# Keyglove_Kit_v0_1.net
KiCad netlist of a schematic drawn in EAGLE
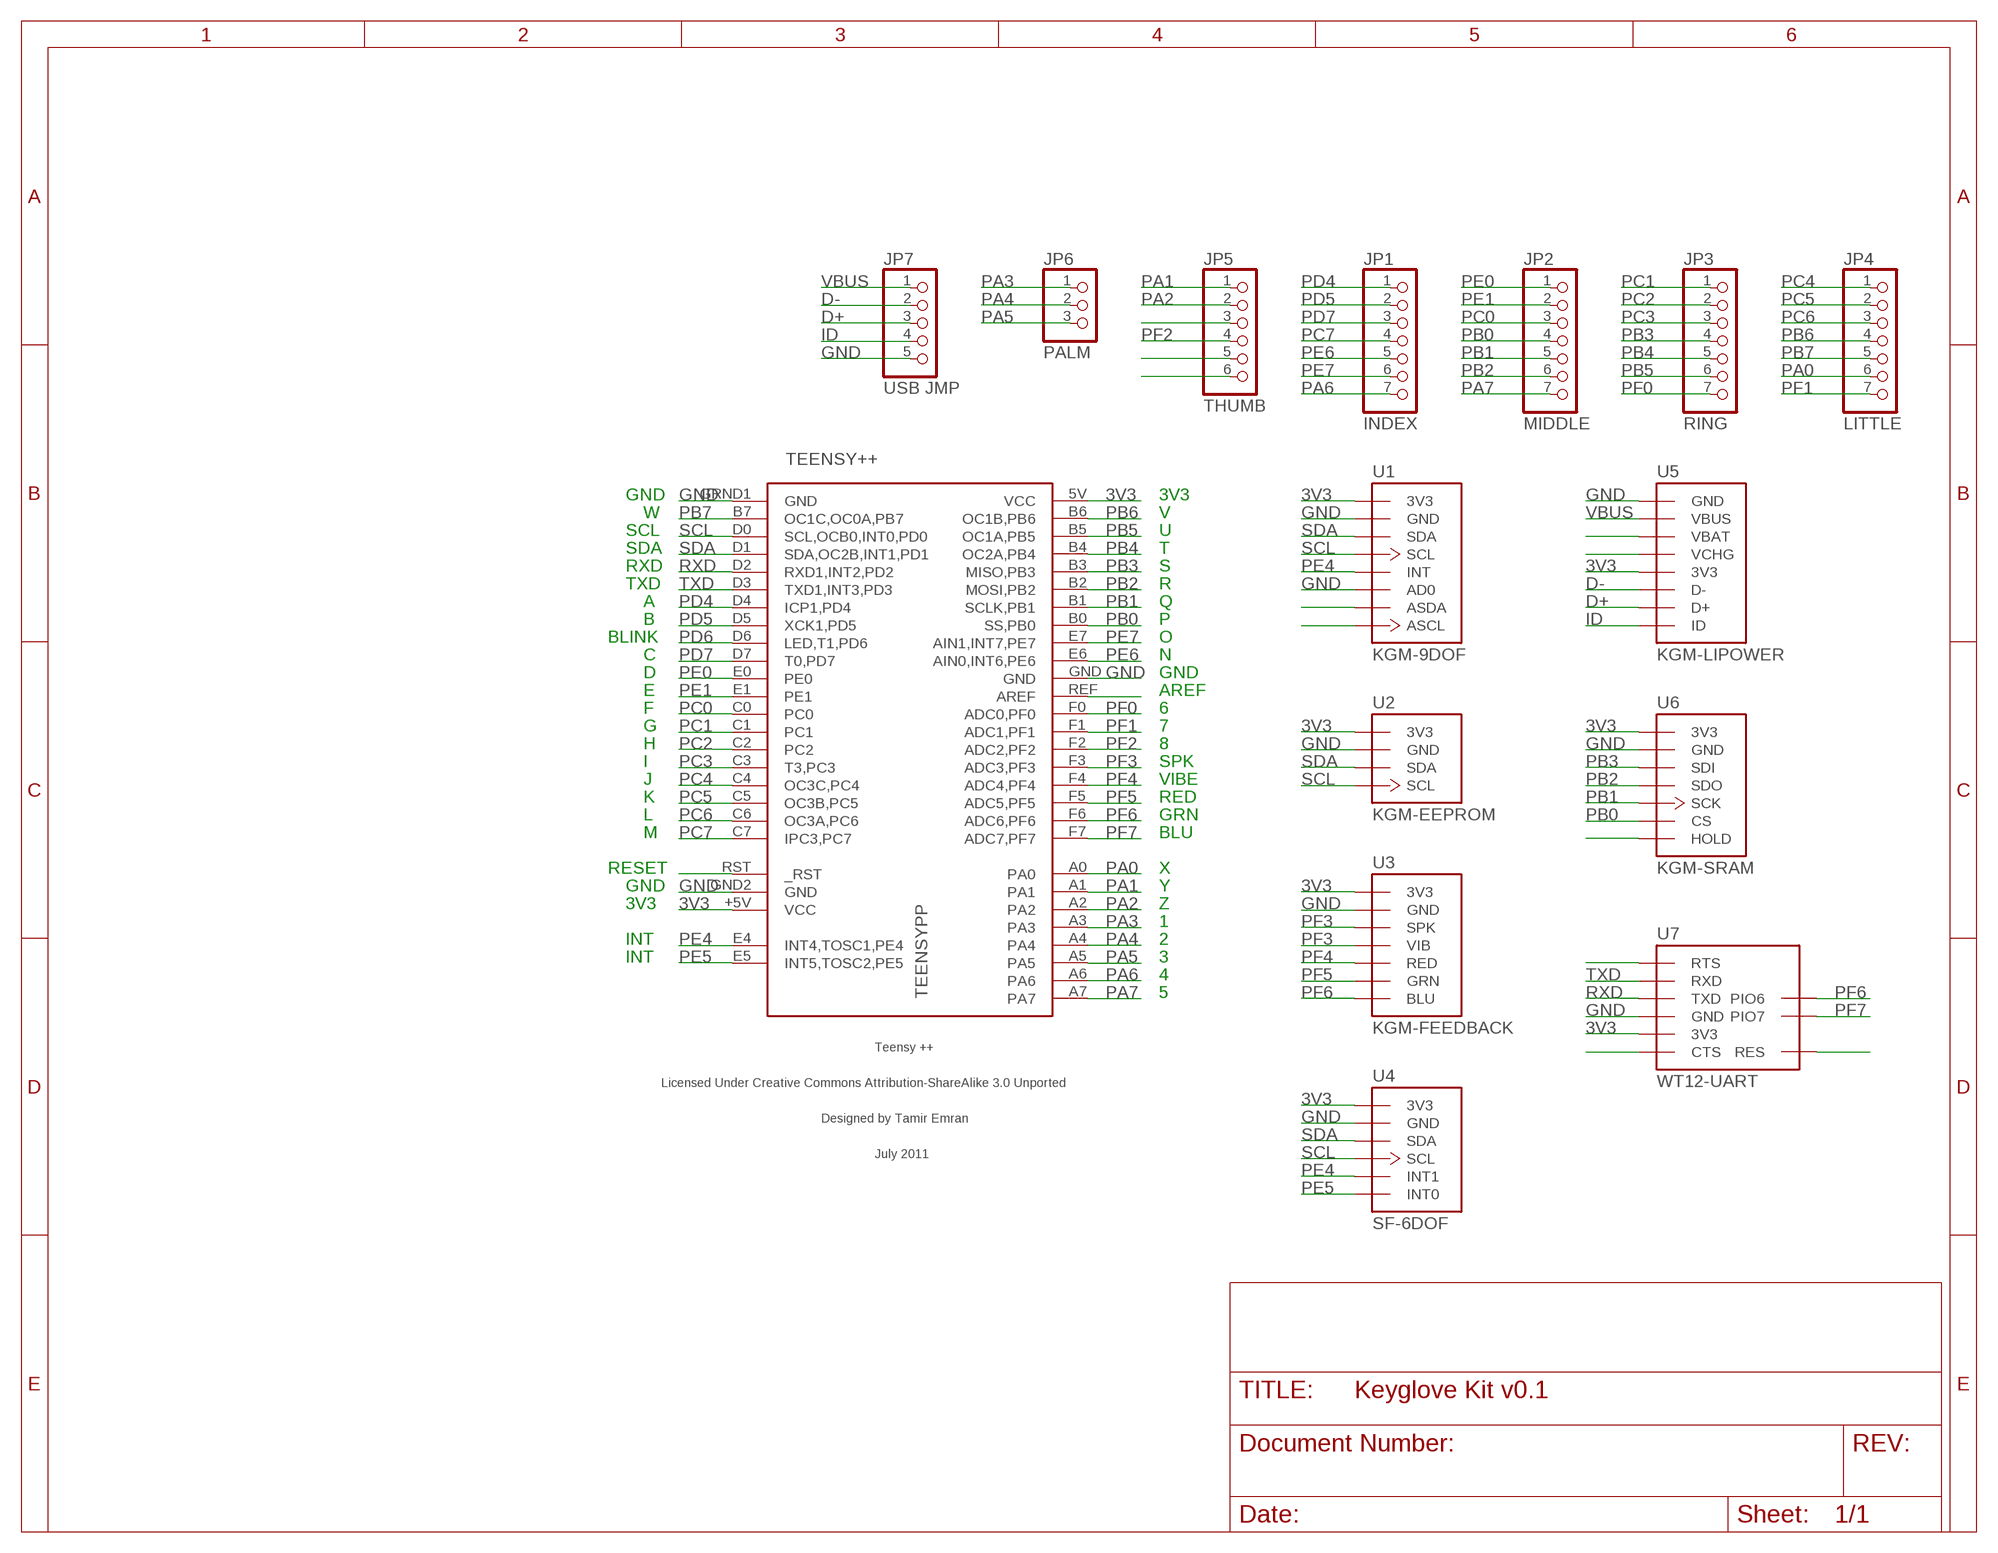
[diagram p0: schematic, sheet 1]

(export (version "E")
  (design (tool "Eeschema 10.0.6"))
  (components
    (comp (ref "JP1")
      (value "INDEX")
      (footprint "eagle-import:1X07")
      (libsource (lib "eagle-import") (part "PINHD-1X7"))
    )
    (comp (ref "JP2")
      (value "MIDDLE")
      (footprint "eagle-import:1X07")
      (libsource (lib "eagle-import") (part "PINHD-1X7"))
    )
    (comp (ref "JP3")
      (value "RING")
      (footprint "eagle-import:1X07")
      (libsource (lib "eagle-import") (part "PINHD-1X7"))
    )
    (comp (ref "JP4")
      (value "LITTLE")
      (footprint "eagle-import:1X07")
      (libsource (lib "eagle-import") (part "PINHD-1X7"))
    )
    (comp (ref "JP5")
      (value "THUMB")
      (footprint "eagle-import:1X06")
      (libsource (lib "eagle-import") (part "PINHD-1X6"))
    )
    (comp (ref "JP6")
      (value "PALM")
      (footprint "eagle-import:1X03")
      (libsource (lib "eagle-import") (part "PINHD-1X3"))
    )
    (comp (ref "JP7")
      (value "USB JMP")
      (footprint "eagle-import:1X05")
      (libsource (lib "eagle-import") (part "PINHD-1X5"))
    )
    (comp (ref "TEENSY++")
      (value "TEENSYPP")
      (footprint "eagle-import:TEENSYPP")
      (libsource (lib "eagle-import") (part "TEENSYPP"))
    )
    (comp (ref "U1")
      (value "KGM-9DOF")
      (footprint "eagle-import:KGM-9DOF")
      (libsource (lib "eagle-import") (part "KGM-9DOF"))
    )
    (comp (ref "U2")
      (value "KGM-EEPROM")
      (footprint "eagle-import:KGM-EEPROM")
      (libsource (lib "eagle-import") (part "KGM-EEPROM"))
    )
    (comp (ref "U3")
      (value "KGM-FEEDBACK")
      (footprint "eagle-import:KGM-FEEDBACK")
      (libsource (lib "eagle-import") (part "KGM-FEEDBACK"))
    )
    (comp (ref "U4")
      (value "SF-6DOF")
      (footprint "eagle-import:SF-6DOF")
      (libsource (lib "eagle-import") (part "SF-6DOF"))
    )
    (comp (ref "U5")
      (value "KGM-LIPOWER")
      (footprint "eagle-import:KGM-LIPOWER")
      (libsource (lib "eagle-import") (part "KGM-LIPOWER"))
    )
    (comp (ref "U6")
      (value "KGM-SRAM")
      (footprint "eagle-import:KGM-SRAM")
      (libsource (lib "eagle-import") (part "KGM-SRAM"))
    )
    (comp (ref "U7")
      (value "WT12-UART")
      (footprint "eagle-import:WT12-UART")
      (libsource (lib "eagle-import") (part "WT12-UART"))
    )
  )
  (nets
    (net (code "1") (name "/3V3") (class "Default")
      (node (ref "TEENSY++") (pin "+5V") (pinfunction "VCC_+5V") (pintype "power_in"))
      (node (ref "TEENSY++") (pin "5V") (pinfunction "VCC_5V") (pintype "power_in"))
      (node (ref "U1") (pin "3V3") (pinfunction "3V3_3V3") (pintype "power_in"))
      (node (ref "U2") (pin "3V3") (pinfunction "3V3_3V3") (pintype "power_in"))
      (node (ref "U3") (pin "3V3") (pinfunction "3V3_3V3") (pintype "power_in"))
      (node (ref "U4") (pin "3V3") (pinfunction "3V3_3V3") (pintype "power_in"))
      (node (ref "U5") (pin "3V3") (pinfunction "3V3_3V3") (pintype "power_in"))
      (node (ref "U6") (pin "3V3") (pinfunction "3V3_3V3") (pintype "power_in"))
      (node (ref "U7") (pin "3V3") (pinfunction "3V3_3V3") (pintype "power_in"))
    )
    (net (code "2") (name "/D+") (class "Default")
      (node (ref "JP7") (pin "3") (pinfunction "3_3") (pintype "passive"))
      (node (ref "U5") (pin "D+") (pinfunction "D+_D+") (pintype "bidirectional"))
    )
    (net (code "3") (name "/D-") (class "Default")
      (node (ref "JP7") (pin "2") (pinfunction "2_2") (pintype "passive"))
      (node (ref "U5") (pin "D-") (pinfunction "D-_D-") (pintype "bidirectional"))
    )
    (net (code "4") (name "/GND") (class "Default")
      (node (ref "JP7") (pin "5") (pinfunction "5_5") (pintype "passive"))
      (node (ref "TEENSY++") (pin "GND") (pinfunction "GND_GND") (pintype "power_in"))
      (node (ref "TEENSY++") (pin "GND2") (pinfunction "GND_GND2") (pintype "power_in"))
      (node (ref "TEENSY++") (pin "GRND1") (pinfunction "GND_GRND1") (pintype "power_in"))
      (node (ref "U1") (pin "AD0") (pinfunction "AD0_AD0") (pintype "input"))
      (node (ref "U1") (pin "GND") (pinfunction "GND_GND") (pintype "power_in"))
      (node (ref "U2") (pin "GND") (pinfunction "GND_GND") (pintype "power_in"))
      (node (ref "U3") (pin "GND") (pinfunction "GND_GND") (pintype "power_in"))
      (node (ref "U4") (pin "GND") (pinfunction "GND_GND") (pintype "power_in"))
      (node (ref "U5") (pin "GND") (pinfunction "GND_GND") (pintype "power_in"))
      (node (ref "U6") (pin "GND") (pinfunction "GND_GND") (pintype "power_in"))
      (node (ref "U7") (pin "GND") (pinfunction "GND_GND") (pintype "power_in"))
    )
    (net (code "5") (name "/ID") (class "Default")
      (node (ref "JP7") (pin "4") (pinfunction "4_4") (pintype "passive"))
      (node (ref "U5") (pin "ID") (pinfunction "ID_ID") (pintype "bidirectional"))
    )
    (net (code "6") (name "/PA0") (class "Default")
      (node (ref "JP4") (pin "6") (pinfunction "6_6") (pintype "passive"))
      (node (ref "TEENSY++") (pin "A0") (pinfunction "PA0_A0") (pintype "bidirectional"))
    )
    (net (code "7") (name "/PA1") (class "Default")
      (node (ref "JP5") (pin "1") (pinfunction "1_1") (pintype "passive"))
      (node (ref "TEENSY++") (pin "A1") (pinfunction "PA1_A1") (pintype "bidirectional"))
    )
    (net (code "8") (name "/PA2") (class "Default")
      (node (ref "JP5") (pin "2") (pinfunction "2_2") (pintype "passive"))
      (node (ref "TEENSY++") (pin "A2") (pinfunction "PA2_A2") (pintype "bidirectional"))
    )
    (net (code "9") (name "/PA3") (class "Default")
      (node (ref "JP6") (pin "1") (pinfunction "1_1") (pintype "passive"))
      (node (ref "TEENSY++") (pin "A3") (pinfunction "PA3_A3") (pintype "bidirectional"))
    )
    (net (code "10") (name "/PA4") (class "Default")
      (node (ref "JP6") (pin "2") (pinfunction "2_2") (pintype "passive"))
      (node (ref "TEENSY++") (pin "A4") (pinfunction "PA4_A4") (pintype "bidirectional"))
    )
    (net (code "11") (name "/PA5") (class "Default")
      (node (ref "JP6") (pin "3") (pinfunction "3_3") (pintype "passive"))
      (node (ref "TEENSY++") (pin "A5") (pinfunction "PA5_A5") (pintype "bidirectional"))
    )
    (net (code "12") (name "/PA6") (class "Default")
      (node (ref "JP1") (pin "7") (pinfunction "7_7") (pintype "passive"))
      (node (ref "TEENSY++") (pin "A6") (pinfunction "PA6_A6") (pintype "bidirectional"))
    )
    (net (code "13") (name "/PA7") (class "Default")
      (node (ref "JP2") (pin "7") (pinfunction "7_7") (pintype "passive"))
      (node (ref "TEENSY++") (pin "A7") (pinfunction "PA7_A7") (pintype "bidirectional"))
    )
    (net (code "14") (name "/PB0") (class "Default")
      (node (ref "JP2") (pin "4") (pinfunction "4_4") (pintype "passive"))
      (node (ref "TEENSY++") (pin "B0") (pinfunction "SS,PB0_B0") (pintype "bidirectional"))
      (node (ref "U6") (pin "CS") (pinfunction "CS_CS") (pintype "input"))
    )
    (net (code "15") (name "/PB1") (class "Default")
      (node (ref "JP2") (pin "5") (pinfunction "5_5") (pintype "passive"))
      (node (ref "TEENSY++") (pin "B1") (pinfunction "SCLK,PB1_B1") (pintype "bidirectional"))
      (node (ref "U6") (pin "SCK") (pinfunction "SCK_SCK") (pintype "bidirectional"))
    )
    (net (code "16") (name "/PB2") (class "Default")
      (node (ref "JP2") (pin "6") (pinfunction "6_6") (pintype "passive"))
      (node (ref "TEENSY++") (pin "B2") (pinfunction "MOSI,PB2_B2") (pintype "bidirectional"))
      (node (ref "U6") (pin "SDO") (pinfunction "SDO_SDO") (pintype "output"))
    )
    (net (code "17") (name "/PB3") (class "Default")
      (node (ref "JP3") (pin "4") (pinfunction "4_4") (pintype "passive"))
      (node (ref "TEENSY++") (pin "B3") (pinfunction "MISO,PB3_B3") (pintype "bidirectional"))
      (node (ref "U6") (pin "SDI") (pinfunction "SDI_SDI") (pintype "input"))
    )
    (net (code "18") (name "/PB4") (class "Default")
      (node (ref "JP3") (pin "5") (pinfunction "5_5") (pintype "passive"))
      (node (ref "TEENSY++") (pin "B4") (pinfunction "OC2A,PB4_B4") (pintype "bidirectional"))
    )
    (net (code "19") (name "/PB5") (class "Default")
      (node (ref "JP3") (pin "6") (pinfunction "6_6") (pintype "passive"))
      (node (ref "TEENSY++") (pin "B5") (pinfunction "OC1A,PB5_B5") (pintype "bidirectional"))
    )
    (net (code "20") (name "/PB6") (class "Default")
      (node (ref "JP4") (pin "4") (pinfunction "4_4") (pintype "passive"))
      (node (ref "TEENSY++") (pin "B6") (pinfunction "OC1B,PB6_B6") (pintype "bidirectional"))
    )
    (net (code "21") (name "/PB7") (class "Default")
      (node (ref "JP4") (pin "5") (pinfunction "5_5") (pintype "passive"))
      (node (ref "TEENSY++") (pin "B7") (pinfunction "OC1C,OC0A,PB7_B7") (pintype "bidirectional"))
    )
    (net (code "22") (name "/PC0") (class "Default")
      (node (ref "JP2") (pin "3") (pinfunction "3_3") (pintype "passive"))
      (node (ref "TEENSY++") (pin "C0") (pinfunction "PC0_C0") (pintype "bidirectional"))
    )
    (net (code "23") (name "/PC1") (class "Default")
      (node (ref "JP3") (pin "1") (pinfunction "1_1") (pintype "passive"))
      (node (ref "TEENSY++") (pin "C1") (pinfunction "PC1_C1") (pintype "bidirectional"))
    )
    (net (code "24") (name "/PC2") (class "Default")
      (node (ref "JP3") (pin "2") (pinfunction "2_2") (pintype "passive"))
      (node (ref "TEENSY++") (pin "C2") (pinfunction "PC2_C2") (pintype "bidirectional"))
    )
    (net (code "25") (name "/PC3") (class "Default")
      (node (ref "JP3") (pin "3") (pinfunction "3_3") (pintype "passive"))
      (node (ref "TEENSY++") (pin "C3") (pinfunction "T3,PC3_C3") (pintype "bidirectional"))
    )
    (net (code "26") (name "/PC4") (class "Default")
      (node (ref "JP4") (pin "1") (pinfunction "1_1") (pintype "passive"))
      (node (ref "TEENSY++") (pin "C4") (pinfunction "OC3C,PC4_C4") (pintype "bidirectional"))
    )
    (net (code "27") (name "/PC5") (class "Default")
      (node (ref "JP4") (pin "2") (pinfunction "2_2") (pintype "passive"))
      (node (ref "TEENSY++") (pin "C5") (pinfunction "OC3B,PC5_C5") (pintype "bidirectional"))
    )
    (net (code "28") (name "/PC6") (class "Default")
      (node (ref "JP4") (pin "3") (pinfunction "3_3") (pintype "passive"))
      (node (ref "TEENSY++") (pin "C6") (pinfunction "OC3A,PC6_C6") (pintype "bidirectional"))
    )
    (net (code "29") (name "/PC7") (class "Default")
      (node (ref "JP1") (pin "4") (pinfunction "4_4") (pintype "passive"))
      (node (ref "TEENSY++") (pin "C7") (pinfunction "IPC3,PC7_C7") (pintype "bidirectional"))
    )
    (net (code "30") (name "/PD4") (class "Default")
      (node (ref "JP1") (pin "1") (pinfunction "1_1") (pintype "passive"))
      (node (ref "TEENSY++") (pin "D4") (pinfunction "ICP1,PD4_D4") (pintype "bidirectional"))
    )
    (net (code "31") (name "/PD5") (class "Default")
      (node (ref "JP1") (pin "2") (pinfunction "2_2") (pintype "passive"))
      (node (ref "TEENSY++") (pin "D5") (pinfunction "XCK1,PD5_D5") (pintype "bidirectional"))
    )
    (net (code "32") (name "/PD6") (class "Default")
      (node (ref "TEENSY++") (pin "D6") (pinfunction "LED,T1,PD6_D6") (pintype "bidirectional"))
    )
    (net (code "33") (name "/PD7") (class "Default")
      (node (ref "JP1") (pin "3") (pinfunction "3_3") (pintype "passive"))
      (node (ref "TEENSY++") (pin "D7") (pinfunction "T0,PD7_D7") (pintype "bidirectional"))
    )
    (net (code "34") (name "/PE0") (class "Default")
      (node (ref "JP2") (pin "1") (pinfunction "1_1") (pintype "passive"))
      (node (ref "TEENSY++") (pin "E0") (pinfunction "PE0_E0") (pintype "bidirectional"))
    )
    (net (code "35") (name "/PE1") (class "Default")
      (node (ref "JP2") (pin "2") (pinfunction "2_2") (pintype "passive"))
      (node (ref "TEENSY++") (pin "E1") (pinfunction "PE1_E1") (pintype "bidirectional"))
    )
    (net (code "36") (name "/PE4") (class "Default")
      (node (ref "TEENSY++") (pin "E4") (pinfunction "INT4,TOSC1,PE4_E4") (pintype "bidirectional"))
      (node (ref "U1") (pin "INT") (pinfunction "INT_INT") (pintype "output"))
      (node (ref "U4") (pin "INT1") (pinfunction "INT1_INT1") (pintype "output"))
    )
    (net (code "37") (name "/PE5") (class "Default")
      (node (ref "TEENSY++") (pin "E5") (pinfunction "INT5,TOSC2,PE5_E5") (pintype "bidirectional"))
      (node (ref "U4") (pin "INT0") (pinfunction "INT0_INT0") (pintype "output"))
    )
    (net (code "38") (name "/PE6") (class "Default")
      (node (ref "JP1") (pin "5") (pinfunction "5_5") (pintype "passive"))
      (node (ref "TEENSY++") (pin "E6") (pinfunction "AIN0,INT6,PE6_E6") (pintype "bidirectional"))
    )
    (net (code "39") (name "/PE7") (class "Default")
      (node (ref "JP1") (pin "6") (pinfunction "6_6") (pintype "passive"))
      (node (ref "TEENSY++") (pin "E7") (pinfunction "AIN1,INT7,PE7_E7") (pintype "bidirectional"))
    )
    (net (code "40") (name "/PF0") (class "Default")
      (node (ref "JP3") (pin "7") (pinfunction "7_7") (pintype "passive"))
      (node (ref "TEENSY++") (pin "F0") (pinfunction "ADC0,PF0_F0") (pintype "bidirectional"))
    )
    (net (code "41") (name "/PF1") (class "Default")
      (node (ref "JP4") (pin "7") (pinfunction "7_7") (pintype "passive"))
      (node (ref "TEENSY++") (pin "F1") (pinfunction "ADC1,PF1_F1") (pintype "bidirectional"))
    )
    (net (code "42") (name "/PF2") (class "Default")
      (node (ref "JP5") (pin "4") (pinfunction "4_4") (pintype "passive"))
      (node (ref "TEENSY++") (pin "F2") (pinfunction "ADC2,PF2_F2") (pintype "bidirectional"))
    )
    (net (code "43") (name "/PF3") (class "Default")
      (node (ref "TEENSY++") (pin "F3") (pinfunction "ADC3,PF3_F3") (pintype "bidirectional"))
      (node (ref "U3") (pin "SPK") (pinfunction "SPK_SPK") (pintype "input"))
      (node (ref "U3") (pin "VIB") (pinfunction "VIB_VIB") (pintype "input"))
    )
    (net (code "44") (name "/PF4") (class "Default")
      (node (ref "TEENSY++") (pin "F4") (pinfunction "ADC4,PF4_F4") (pintype "bidirectional"))
      (node (ref "U3") (pin "RED") (pinfunction "RED_RED") (pintype "input"))
    )
    (net (code "45") (name "/PF5") (class "Default")
      (node (ref "TEENSY++") (pin "F5") (pinfunction "ADC5,PF5_F5") (pintype "bidirectional"))
      (node (ref "U3") (pin "GRN") (pinfunction "GRN_GRN") (pintype "input"))
    )
    (net (code "46") (name "/PF6") (class "Default")
      (node (ref "TEENSY++") (pin "F6") (pinfunction "ADC6,PF6_F6") (pintype "bidirectional"))
      (node (ref "U3") (pin "BLUE") (pinfunction "BLU_BLUE") (pintype "input"))
      (node (ref "U7") (pin "PIO6") (pinfunction "PIO6_PIO6") (pintype "bidirectional"))
    )
    (net (code "47") (name "/PF7") (class "Default")
      (node (ref "TEENSY++") (pin "F7") (pinfunction "ADC7,PF7_F7") (pintype "bidirectional"))
      (node (ref "U7") (pin "PIO7") (pinfunction "PIO7_PIO7") (pintype "bidirectional"))
    )
    (net (code "48") (name "/RXD") (class "Default")
      (node (ref "TEENSY++") (pin "D2") (pinfunction "RXD1,INT2,PD2_D2") (pintype "bidirectional"))
      (node (ref "U7") (pin "TXD") (pinfunction "TXD_TXD") (pintype "output"))
    )
    (net (code "49") (name "/SCL") (class "Default")
      (node (ref "TEENSY++") (pin "D0") (pinfunction "SCL,OCB0,INT0,PD0_D0") (pintype "bidirectional"))
      (node (ref "U1") (pin "SCL") (pinfunction "SCL_SCL") (pintype "bidirectional"))
      (node (ref "U2") (pin "SCL") (pinfunction "SCL_SCL") (pintype "bidirectional"))
      (node (ref "U4") (pin "SCL") (pinfunction "SCL_SCL") (pintype "bidirectional"))
    )
    (net (code "50") (name "/SDA") (class "Default")
      (node (ref "TEENSY++") (pin "D1") (pinfunction "SDA,OC2B,INT1,PD1_D1") (pintype "bidirectional"))
      (node (ref "U1") (pin "SDA") (pinfunction "SDA_SDA") (pintype "bidirectional"))
      (node (ref "U2") (pin "SDA") (pinfunction "SDA_SDA") (pintype "bidirectional"))
      (node (ref "U4") (pin "SDA") (pinfunction "SDA_SDA") (pintype "bidirectional"))
    )
    (net (code "51") (name "/TXD") (class "Default")
      (node (ref "TEENSY++") (pin "D3") (pinfunction "TXD1,INT3,PD3_D3") (pintype "bidirectional"))
      (node (ref "U7") (pin "RXD") (pinfunction "RXD_RXD") (pintype "input"))
    )
    (net (code "52") (name "/VBUS") (class "Default")
      (node (ref "JP7") (pin "1") (pinfunction "1_1") (pintype "passive"))
      (node (ref "U5") (pin "VBUS") (pinfunction "VBUS_VBUS") (pintype "power_in"))
    )
    (net (code "53") (name "unconnected-(JP5-Pad3)") (class "Default")
      (node (ref "JP5") (pin "3") (pinfunction "3_3") (pintype "passive"))
    )
    (net (code "54") (name "unconnected-(JP5-Pad5)") (class "Default")
      (node (ref "JP5") (pin "5") (pinfunction "5_5") (pintype "passive"))
    )
    (net (code "55") (name "unconnected-(JP5-Pad6)") (class "Default")
      (node (ref "JP5") (pin "6") (pinfunction "6_6") (pintype "passive"))
    )
    (net (code "56") (name "unconnected-(TEENSY++-AREF-PadREF)") (class "Default")
      (node (ref "TEENSY++") (pin "REF") (pinfunction "AREF_REF") (pintype "input"))
    )
    (net (code "57") (name "unconnected-(TEENSY++-_RST-PadRST)") (class "Default")
      (node (ref "TEENSY++") (pin "RST") (pinfunction "_RST_RST") (pintype "input"))
    )
    (net (code "58") (name "unconnected-(U1-PadASCL)") (class "Default")
      (node (ref "U1") (pin "ASCL") (pinfunction "ASCL_ASCL") (pintype "bidirectional"))
    )
    (net (code "59") (name "unconnected-(U1-PadASDA)") (class "Default")
      (node (ref "U1") (pin "ASDA") (pinfunction "ASDA_ASDA") (pintype "bidirectional"))
    )
    (net (code "60") (name "unconnected-(U5-PadVBAT)") (class "Default")
      (node (ref "U5") (pin "VBAT") (pinfunction "VBAT_VBAT") (pintype "power_in"))
    )
    (net (code "61") (name "unconnected-(U5-PadVCHG)") (class "Default")
      (node (ref "U5") (pin "VCHG") (pinfunction "VCHG_VCHG") (pintype "power_in"))
    )
    (net (code "62") (name "unconnected-(U6-PadHOLD)") (class "Default")
      (node (ref "U6") (pin "HOLD") (pinfunction "HOLD_HOLD") (pintype "input"))
    )
    (net (code "63") (name "unconnected-(U7-PadCTS)") (class "Default")
      (node (ref "U7") (pin "CTS") (pinfunction "CTS_CTS") (pintype "input"))
    )
    (net (code "64") (name "unconnected-(U7-PadRTS)") (class "Default")
      (node (ref "U7") (pin "RTS") (pinfunction "RTS_RTS") (pintype "output"))
    )
    (net (code "65") (name "unconnected-(U7-RES-PadRESET)") (class "Default")
      (node (ref "U7") (pin "RESET") (pinfunction "RES_RESET") (pintype "input"))
    )
  )
)
